# mcp23017_loopback_ver_b.net
KiCad netlist of a schematic drawn in Altium Designer
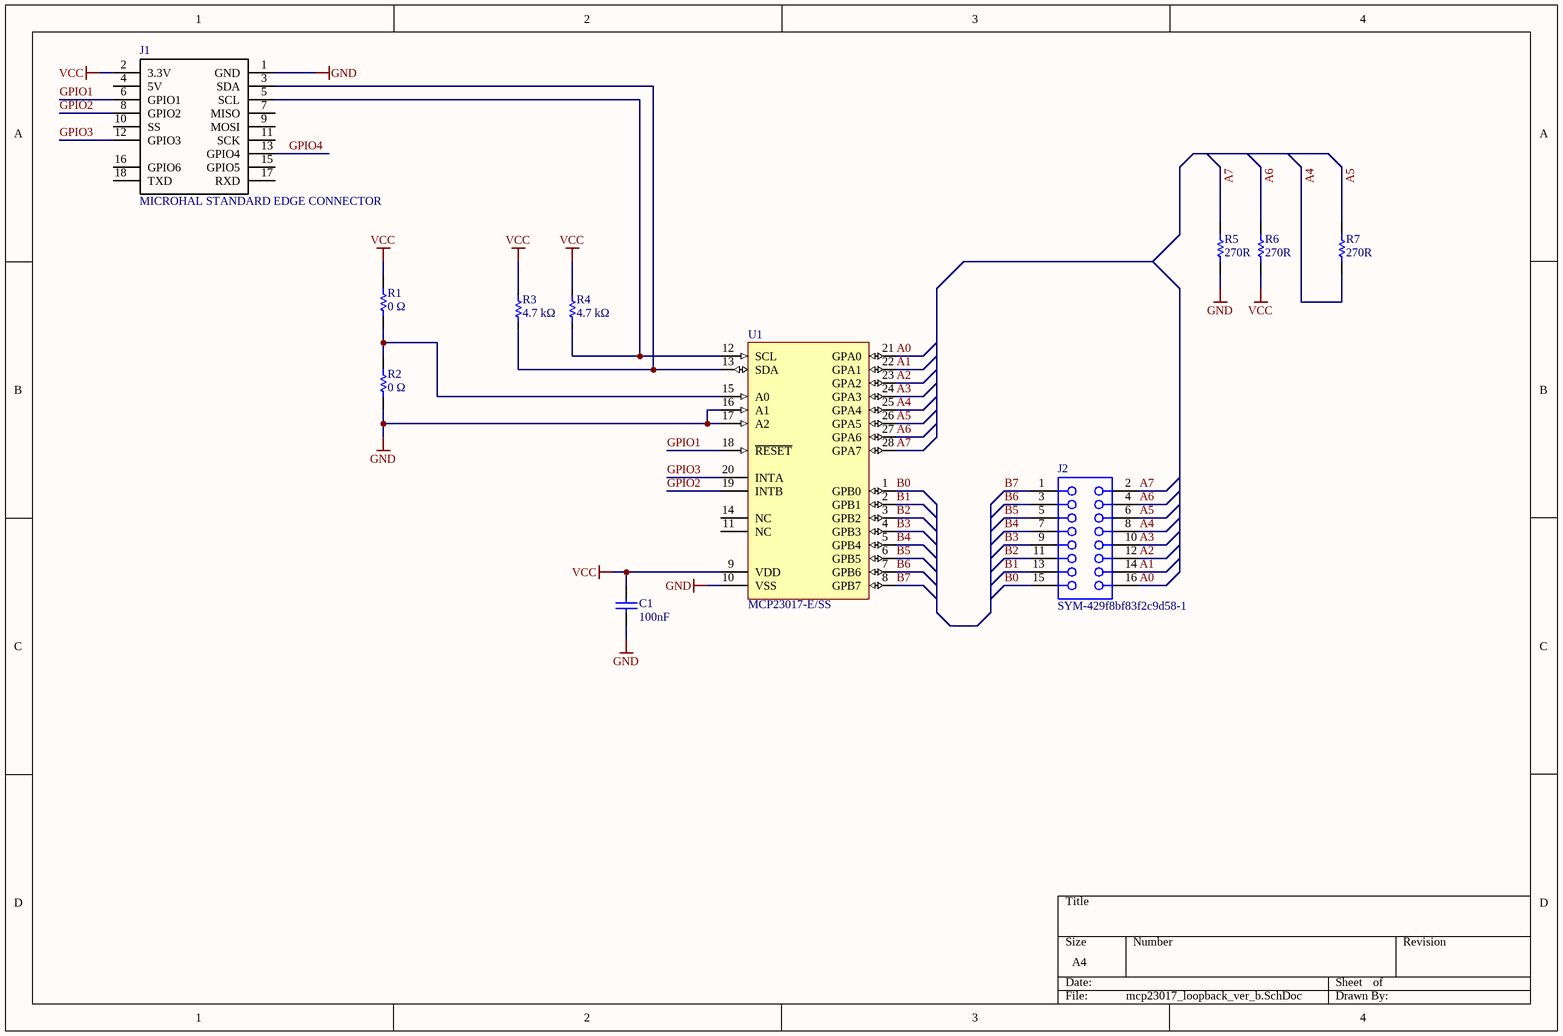
[diagram p0: mcp23017_loopback_ver_b.SchDoc]

(export (version "E")
  (design (tool "Eeschema 10.0.6"))
  (components
    (comp (ref "C1")
      (value "Murata GCM188R71H104KA57D")
      (footprint "CAPC1608X90X35ML10T15")
      (description "CAP CER 0.1UF 50V 10% X7R 0603")
      (fields (field (name "CAPACITANCE") "100nF"))
      (libsource (lib "CommunityVault") (part "CMP-119667-3"))
    )
    (comp (ref "J1")
      (value "MICROHAL STANDARD EDGE CONNECTOR")
      (footprint "PCB-n61ghpg3sznbl2uw6fwj-1")
      (description "microhal standard edge connector with 17 pins")
      (libsource (lib "CommunityVault") (part "CMP-6a3uyflm72uf0am1b36s-2"))
    )
    (comp (ref "J2")
      (value "SYM-429f8bf83f2c9d58-1")
      (footprint "HEADER8X2")
      (description "Conn Unshrouded Header HDR 16 POS 2.54mm Solder ST Thru-Hole Poly Bag")
      (libsource (lib "CommunityVault") (part "CMP-429f8bf83f2c9d58-5"))
    )
    (comp (ref "R1")
      (value "0 Ω")
      (footprint "RESC1608X05N")
      (description "RCA Series 0603 0.1 W 0 O Jumper Surface Mount Thick Film Chip Resistor")
      (fields (field (name "MANUFACTURER PART NUMBER") "RCA06030000ZSEA"))
      (libsource (lib "CommunityVault") (part "SYM-31acf99032f6ee6b-1"))
    )
    (comp (ref "R2")
      (value "0 Ω")
      (footprint "RESC1608X05N")
      (description "RCA Series 0603 0.1 W 0 O Jumper Surface Mount Thick Film Chip Resistor")
      (fields (field (name "MANUFACTURER PART NUMBER") "RCA06030000ZSEA"))
      (libsource (lib "CommunityVault") (part "SYM-31acf99032f6ee6b-1"))
    )
    (comp (ref "R3")
      (value "CRCW06034K70FKEAHP")
      (footprint "PCB-cmzy4aezi5zhn2bew7lt-1")
      (description "Surface Mount Chip Resistor, Thick Film, AEC-Q200 CRCW Series, 4.7 kohm, 250 mW, 1%, 75 V")
      (fields (field (name "RESISTANCE") "4.7 kΩ"))
      (libsource (lib "CommunityVault") (part "CMP-40e08b60e91c9f27-1"))
    )
    (comp (ref "R4")
      (value "CRCW06034K70FKEAHP")
      (footprint "PCB-cmzy4aezi5zhn2bew7lt-1")
      (description "Surface Mount Chip Resistor, Thick Film, AEC-Q200 CRCW Series, 4.7 kohm, 250 mW, 1%, 75 V")
      (fields (field (name "RESISTANCE") "4.7 kΩ"))
      (libsource (lib "CommunityVault") (part "CMP-40e08b60e91c9f27-1"))
    )
    (comp (ref "R5")
      (value "270R")
      (footprint "RESC1608X05N")
      (description "RCA Series 0603 0.1 W 0 O Jumper Surface Mount Thick Film Chip Resistor")
      (fields (field (name "MANUFACTURER PART NUMBER") "RCA06030000ZSEA"))
      (libsource (lib "CommunityVault") (part "SYM-31acf99032f6ee6b-1"))
    )
    (comp (ref "R6")
      (value "270R")
      (footprint "RESC1608X05N")
      (description "RCA Series 0603 0.1 W 0 O Jumper Surface Mount Thick Film Chip Resistor")
      (fields (field (name "MANUFACTURER PART NUMBER") "RCA06030000ZSEA"))
      (libsource (lib "CommunityVault") (part "SYM-31acf99032f6ee6b-1"))
    )
    (comp (ref "R7")
      (value "270R")
      (footprint "RESC1608X05N")
      (description "RCA Series 0603 0.1 W 0 O Jumper Surface Mount Thick Film Chip Resistor")
      (fields (field (name "MANUFACTURER PART NUMBER") "RCA06030000ZSEA"))
      (libsource (lib "CommunityVault") (part "SYM-31acf99032f6ee6b-1"))
    )
    (comp (ref "U1")
      (value "MCP23017-E/SS")
      (footprint "SSOP-SS28_N")
      (description "16-Bit I/O Expander with Serial Interface, 28-Pin SSOP, Extended Temperature")
      (libsource (lib "CommunityVault") (part "PR-BUSIC-MCP23017-28"))
    )
  )
  (nets
    (net (code "1") (name "/A0") (class "Default")
      (node (ref "J2") (pin "16") (pinfunction "16_16") (pintype "passive"))
      (node (ref "U1") (pin "21") (pinfunction "GPA0_21") (pintype "bidirectional"))
    )
    (net (code "2") (name "/A1") (class "Default")
      (node (ref "J2") (pin "14") (pinfunction "14_14") (pintype "passive"))
      (node (ref "U1") (pin "22") (pinfunction "GPA1_22") (pintype "bidirectional"))
    )
    (net (code "3") (name "/A2") (class "Default")
      (node (ref "J2") (pin "12") (pinfunction "12_12") (pintype "passive"))
      (node (ref "U1") (pin "23") (pinfunction "GPA2_23") (pintype "bidirectional"))
    )
    (net (code "4") (name "/A3") (class "Default")
      (node (ref "J2") (pin "10") (pinfunction "10_10") (pintype "passive"))
      (node (ref "U1") (pin "24") (pinfunction "GPA3_24") (pintype "bidirectional"))
    )
    (net (code "5") (name "/A4") (class "Default")
      (node (ref "J2") (pin "8") (pinfunction "8_8") (pintype "passive"))
      (node (ref "R7") (pin "2") (pinfunction "2_2") (pintype "passive"))
      (node (ref "U1") (pin "25") (pinfunction "GPA4_25") (pintype "bidirectional"))
    )
    (net (code "6") (name "/A5") (class "Default")
      (node (ref "J2") (pin "6") (pinfunction "6_6") (pintype "passive"))
      (node (ref "R7") (pin "1") (pinfunction "1_1") (pintype "passive"))
      (node (ref "U1") (pin "26") (pinfunction "GPA5_26") (pintype "bidirectional"))
    )
    (net (code "7") (name "/A6") (class "Default")
      (node (ref "J2") (pin "4") (pinfunction "4_4") (pintype "passive"))
      (node (ref "R6") (pin "2") (pinfunction "2_2") (pintype "passive"))
      (node (ref "U1") (pin "27") (pinfunction "GPA6_27") (pintype "bidirectional"))
    )
    (net (code "8") (name "/A7") (class "Default")
      (node (ref "J2") (pin "2") (pinfunction "2_2") (pintype "passive"))
      (node (ref "R5") (pin "2") (pinfunction "2_2") (pintype "passive"))
      (node (ref "U1") (pin "28") (pinfunction "GPA7_28") (pintype "bidirectional"))
    )
    (net (code "9") (name "/B0") (class "Default")
      (node (ref "J2") (pin "15") (pinfunction "15_15") (pintype "passive"))
      (node (ref "U1") (pin "1") (pinfunction "GPB0_1") (pintype "bidirectional"))
    )
    (net (code "10") (name "/B1") (class "Default")
      (node (ref "J2") (pin "13") (pinfunction "13_13") (pintype "passive"))
      (node (ref "U1") (pin "2") (pinfunction "GPB1_2") (pintype "bidirectional"))
    )
    (net (code "11") (name "/B2") (class "Default")
      (node (ref "J2") (pin "11") (pinfunction "11_11") (pintype "passive"))
      (node (ref "U1") (pin "3") (pinfunction "GPB2_3") (pintype "bidirectional"))
    )
    (net (code "12") (name "/B3") (class "Default")
      (node (ref "J2") (pin "9") (pinfunction "9_9") (pintype "passive"))
      (node (ref "U1") (pin "4") (pinfunction "GPB3_4") (pintype "bidirectional"))
    )
    (net (code "13") (name "/B4") (class "Default")
      (node (ref "J2") (pin "7") (pinfunction "7_7") (pintype "passive"))
      (node (ref "U1") (pin "5") (pinfunction "GPB4_5") (pintype "bidirectional"))
    )
    (net (code "14") (name "/B5") (class "Default")
      (node (ref "J2") (pin "5") (pinfunction "5_5") (pintype "passive"))
      (node (ref "U1") (pin "6") (pinfunction "GPB5_6") (pintype "bidirectional"))
    )
    (net (code "15") (name "/B6") (class "Default")
      (node (ref "J2") (pin "3") (pinfunction "3_3") (pintype "passive"))
      (node (ref "U1") (pin "7") (pinfunction "GPB6_7") (pintype "bidirectional"))
    )
    (net (code "16") (name "/B7") (class "Default")
      (node (ref "J2") (pin "1") (pinfunction "1_1") (pintype "passive"))
      (node (ref "U1") (pin "8") (pinfunction "GPB7_8") (pintype "bidirectional"))
    )
    (net (code "17") (name "/GPIO1") (class "Default")
      (node (ref "J1") (pin "6") (pinfunction "GPIO1_6") (pintype "passive"))
      (node (ref "U1") (pin "18") (pinfunction "~{RESET}_18") (pintype "input"))
    )
    (net (code "18") (name "/GPIO2") (class "Default")
      (node (ref "J1") (pin "8") (pinfunction "GPIO2_8") (pintype "passive"))
      (node (ref "U1") (pin "19") (pinfunction "INTB_19") (pintype "open_collector"))
    )
    (net (code "19") (name "/GPIO3") (class "Default")
      (node (ref "J1") (pin "12") (pinfunction "GPIO3_12") (pintype "passive"))
      (node (ref "U1") (pin "20") (pinfunction "INTA_20") (pintype "open_collector"))
    )
    (net (code "20") (name "/GPIO4") (class "Default")
      (node (ref "J1") (pin "13") (pinfunction "GPIO4_13") (pintype "passive"))
    )
    (net (code "21") (name "GND") (class "Default")
      (node (ref "C1") (pin "2") (pinfunction "2_2") (pintype "passive"))
      (node (ref "J1") (pin "1") (pinfunction "GND_1") (pintype "passive"))
      (node (ref "R2") (pin "1") (pinfunction "1_1") (pintype "passive"))
      (node (ref "R5") (pin "1") (pinfunction "1_1") (pintype "passive"))
      (node (ref "U1") (pin "10") (pinfunction "VSS_10") (pintype "power_in"))
      (node (ref "U1") (pin "16") (pinfunction "A1_16") (pintype "input"))
      (node (ref "U1") (pin "17") (pinfunction "A2_17") (pintype "input"))
    )
    (net (code "22") (name "Net-(J1-SCL)") (class "Default")
      (node (ref "J1") (pin "5") (pinfunction "SCL_5") (pintype "passive"))
      (node (ref "R4") (pin "2") (pinfunction "2_2") (pintype "passive"))
      (node (ref "U1") (pin "12") (pinfunction "SCL_12") (pintype "input"))
    )
    (net (code "23") (name "Net-(J1-SDA)") (class "Default")
      (node (ref "J1") (pin "3") (pinfunction "SDA_3") (pintype "passive"))
      (node (ref "R3") (pin "2") (pinfunction "2_2") (pintype "passive"))
      (node (ref "U1") (pin "13") (pinfunction "SDA_13") (pintype "bidirectional"))
    )
    (net (code "24") (name "Net-(U1-A0)") (class "Default")
      (node (ref "R1") (pin "1") (pinfunction "1_1") (pintype "passive"))
      (node (ref "R2") (pin "2") (pinfunction "2_2") (pintype "passive"))
      (node (ref "U1") (pin "15") (pinfunction "A0_15") (pintype "input"))
    )
    (net (code "25") (name "VCC") (class "Default")
      (node (ref "C1") (pin "1") (pinfunction "1_1") (pintype "passive"))
      (node (ref "J1") (pin "2") (pinfunction "3.3V_2") (pintype "passive"))
      (node (ref "R1") (pin "2") (pinfunction "2_2") (pintype "passive"))
      (node (ref "R3") (pin "1") (pinfunction "1_1") (pintype "passive"))
      (node (ref "R4") (pin "1") (pinfunction "1_1") (pintype "passive"))
      (node (ref "R6") (pin "1") (pinfunction "1_1") (pintype "passive"))
      (node (ref "U1") (pin "9") (pinfunction "VDD_9") (pintype "power_in"))
    )
    (net (code "26") (name "unconnected-(J1-5V-Pad4)") (class "Default")
      (node (ref "J1") (pin "4") (pinfunction "5V_4") (pintype "passive"))
    )
    (net (code "27") (name "unconnected-(J1-GPIO5-Pad15)") (class "Default")
      (node (ref "J1") (pin "15") (pinfunction "GPIO5_15") (pintype "passive"))
    )
    (net (code "28") (name "unconnected-(J1-GPIO6-Pad16)") (class "Default")
      (node (ref "J1") (pin "16") (pinfunction "GPIO6_16") (pintype "passive"))
    )
    (net (code "29") (name "unconnected-(J1-MISO-Pad7)") (class "Default")
      (node (ref "J1") (pin "7") (pinfunction "MISO_7") (pintype "passive"))
    )
    (net (code "30") (name "unconnected-(J1-MOSI-Pad9)") (class "Default")
      (node (ref "J1") (pin "9") (pinfunction "MOSI_9") (pintype "passive"))
    )
    (net (code "31") (name "unconnected-(J1-RXD-Pad17)") (class "Default")
      (node (ref "J1") (pin "17") (pinfunction "RXD_17") (pintype "passive"))
    )
    (net (code "32") (name "unconnected-(J1-SCK-Pad11)") (class "Default")
      (node (ref "J1") (pin "11") (pinfunction "SCK_11") (pintype "passive"))
    )
    (net (code "33") (name "unconnected-(J1-SS-Pad10)") (class "Default")
      (node (ref "J1") (pin "10") (pinfunction "SS_10") (pintype "passive"))
    )
    (net (code "34") (name "unconnected-(J1-TXD-Pad18)") (class "Default")
      (node (ref "J1") (pin "18") (pinfunction "TXD_18") (pintype "passive"))
    )
    (net (code "35") (name "unconnected-(U1-NC-Pad11)") (class "Default")
      (node (ref "U1") (pin "11") (pinfunction "NC_11") (pintype "passive"))
    )
    (net (code "36") (name "unconnected-(U1-NC-Pad14)") (class "Default")
      (node (ref "U1") (pin "14") (pinfunction "NC_14") (pintype "passive"))
    )
  )
)
